# OpIoT_jetson_v_1_5.net
KiCad netlist of a schematic drawn in EAGLE
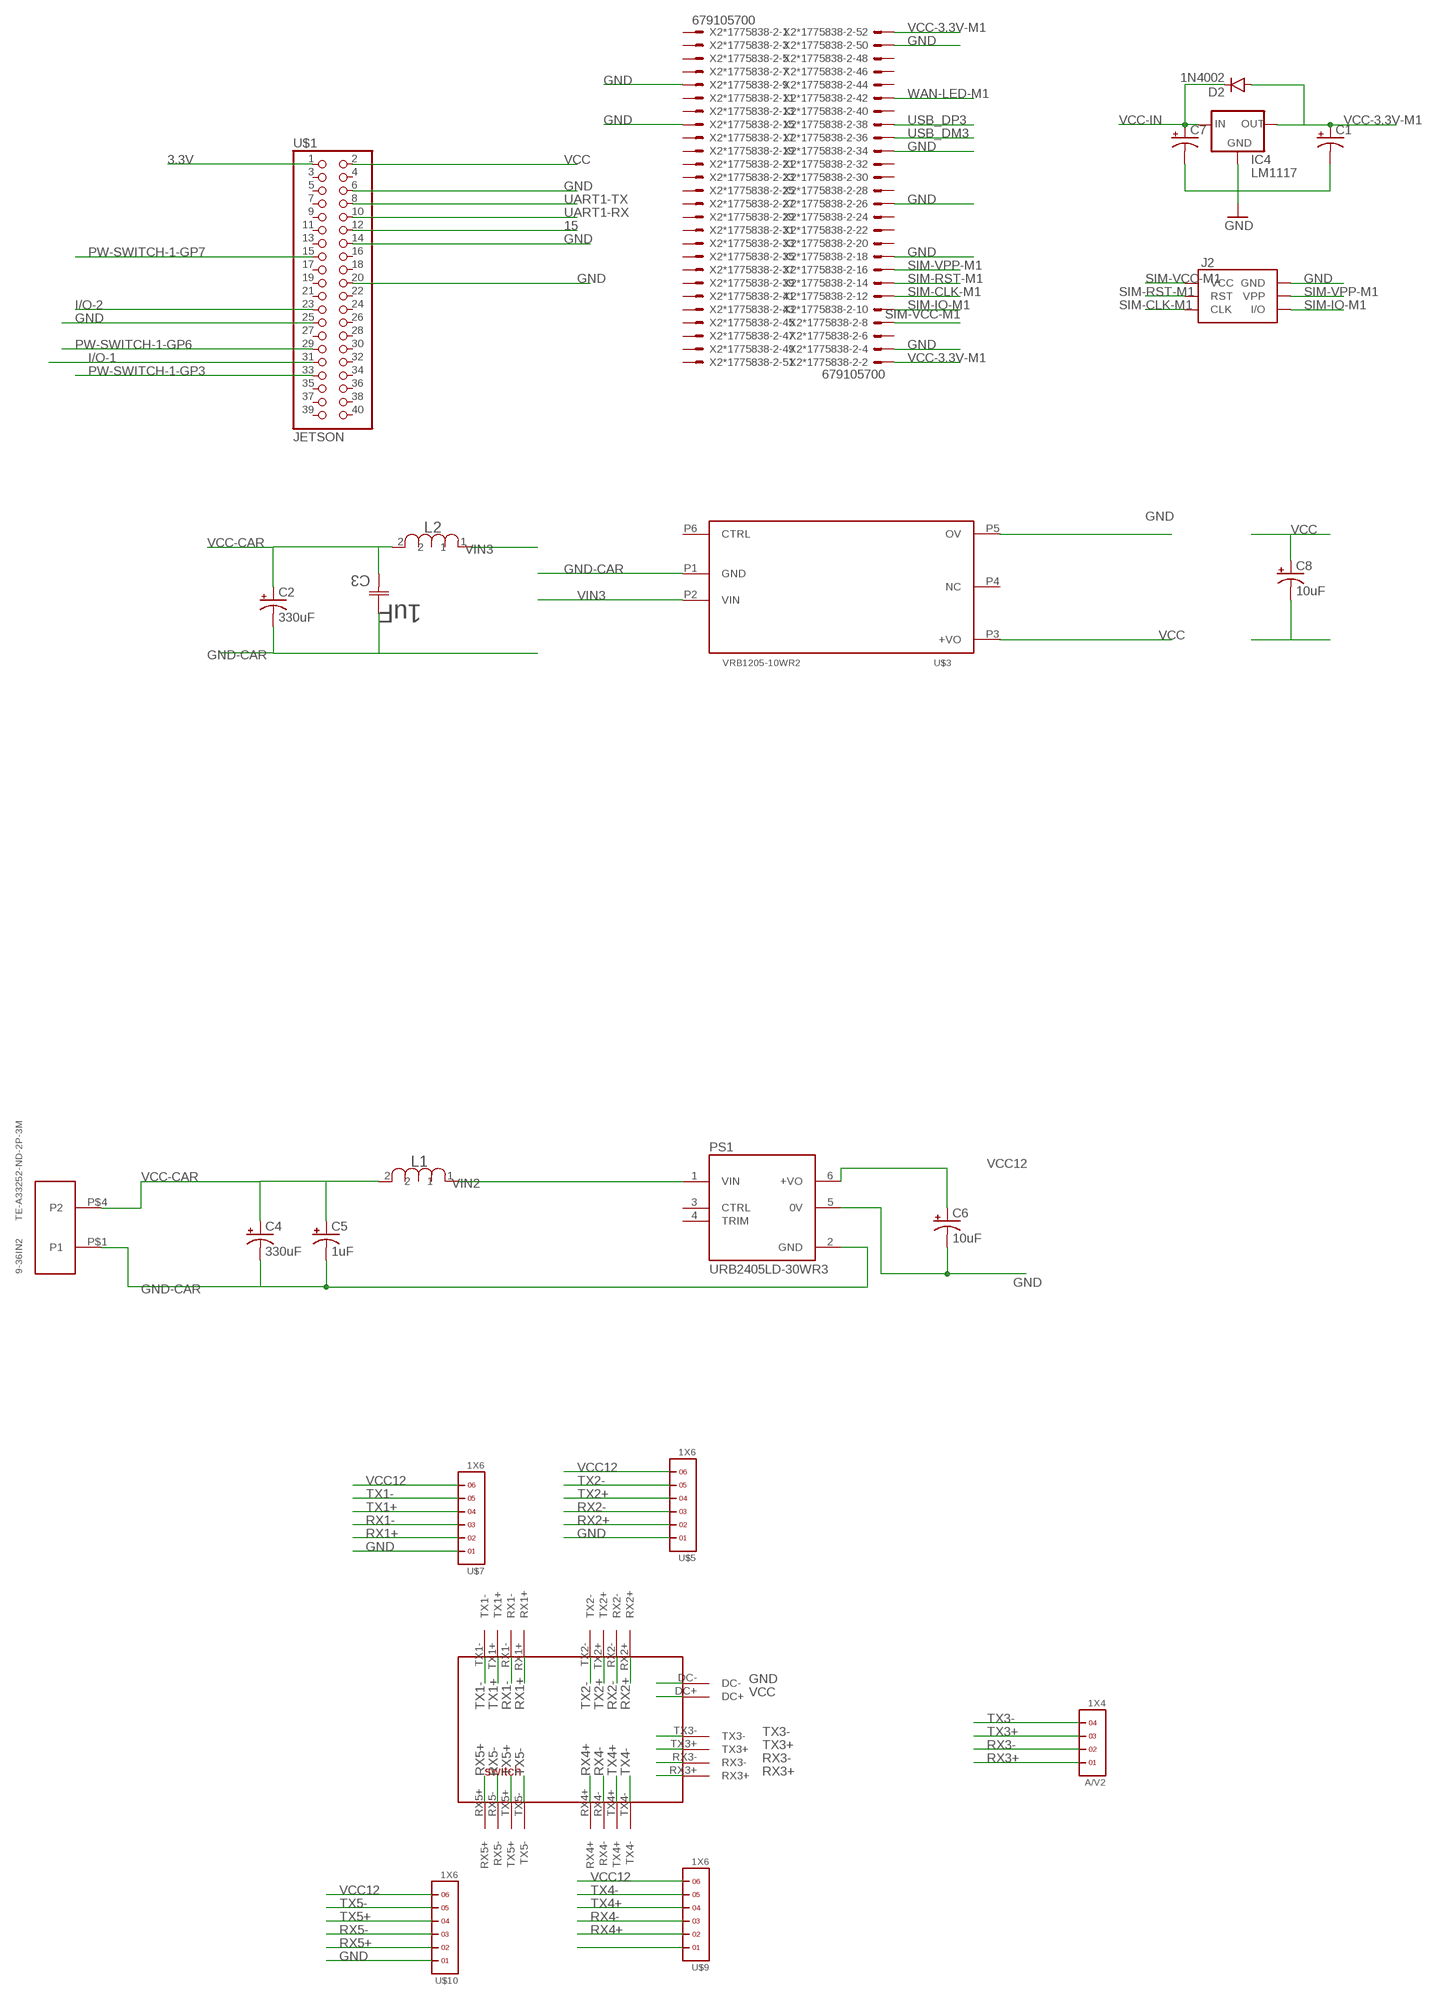
[diagram p0: schematic, sheet 1, part 1 of 3]
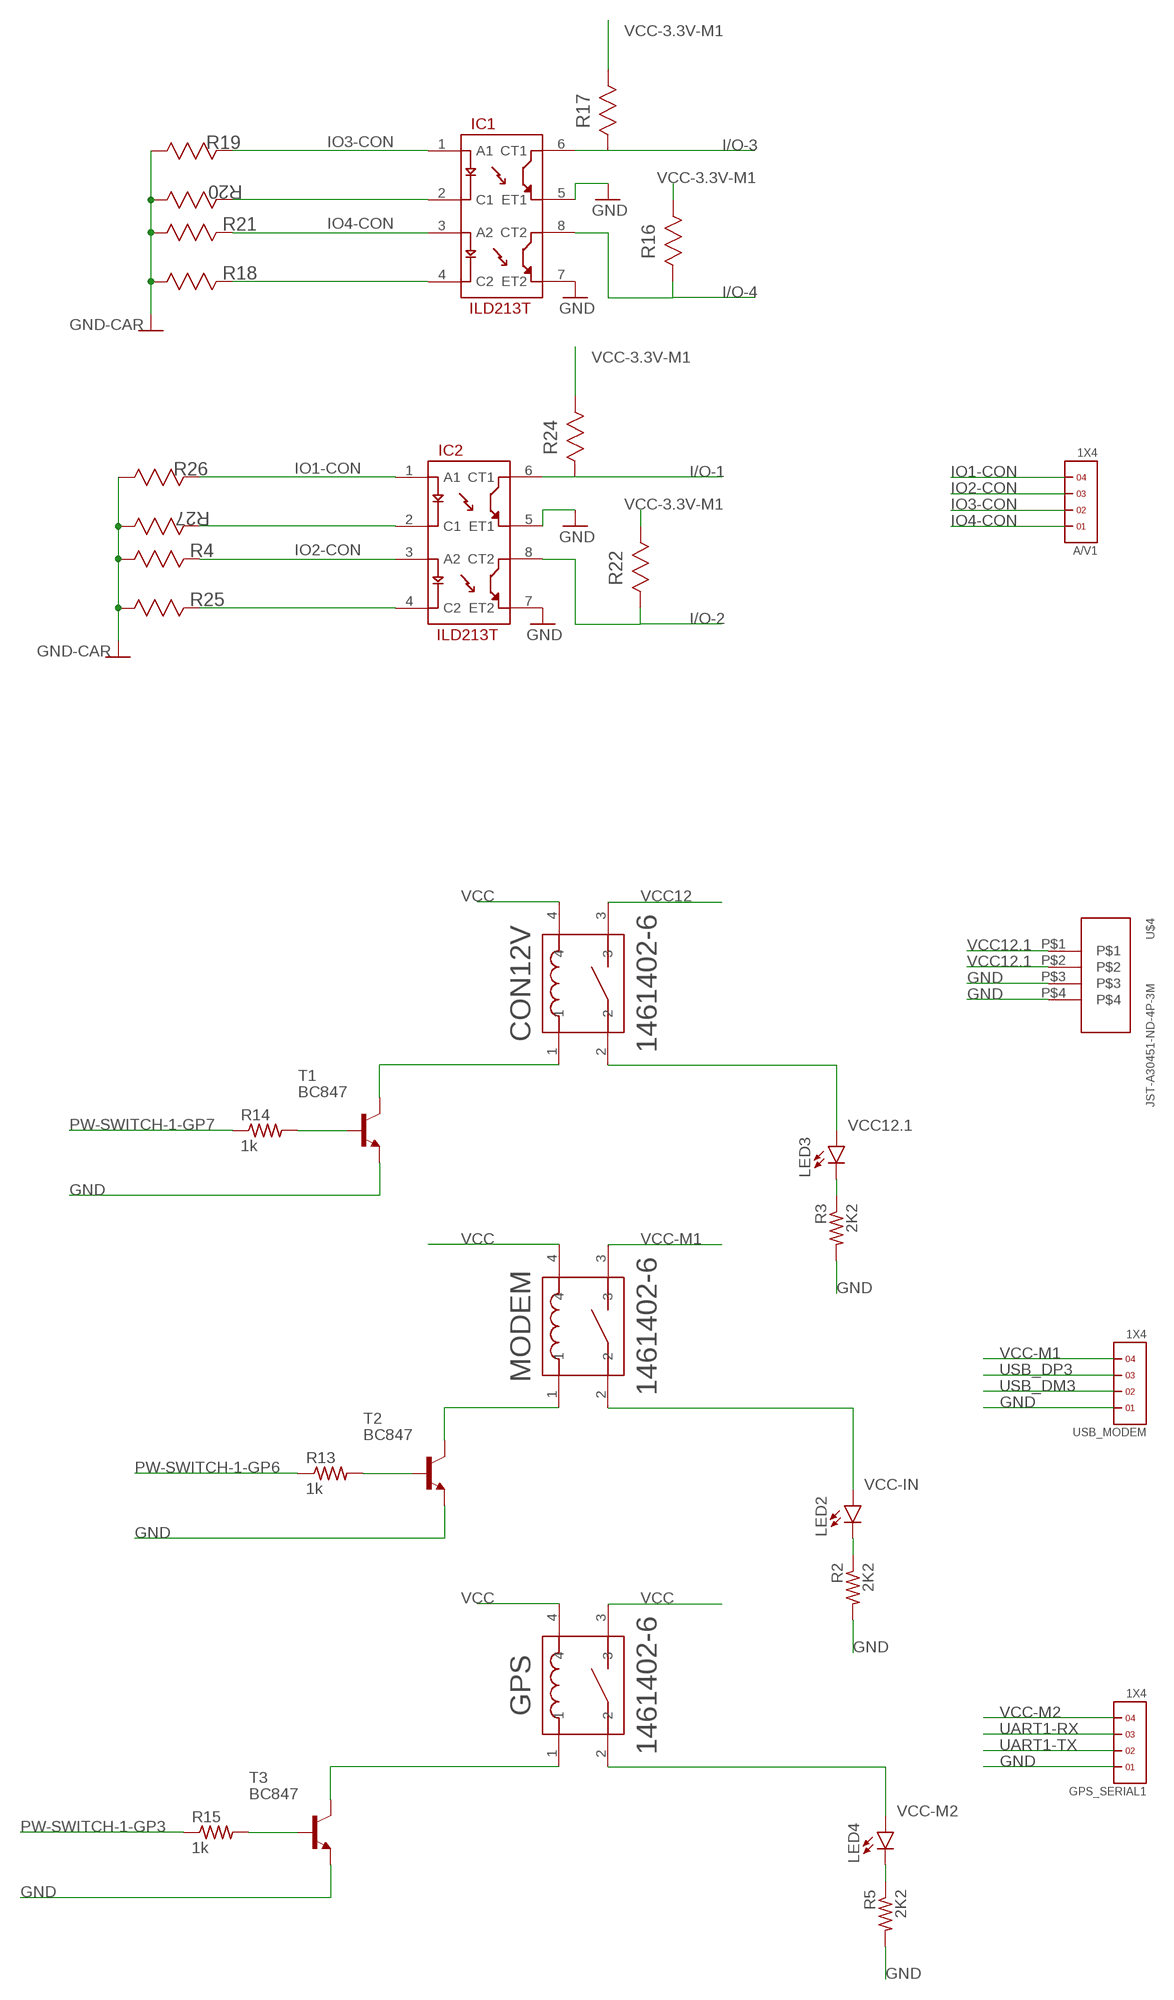
[diagram p1: schematic, sheet 1, part 2 of 3]
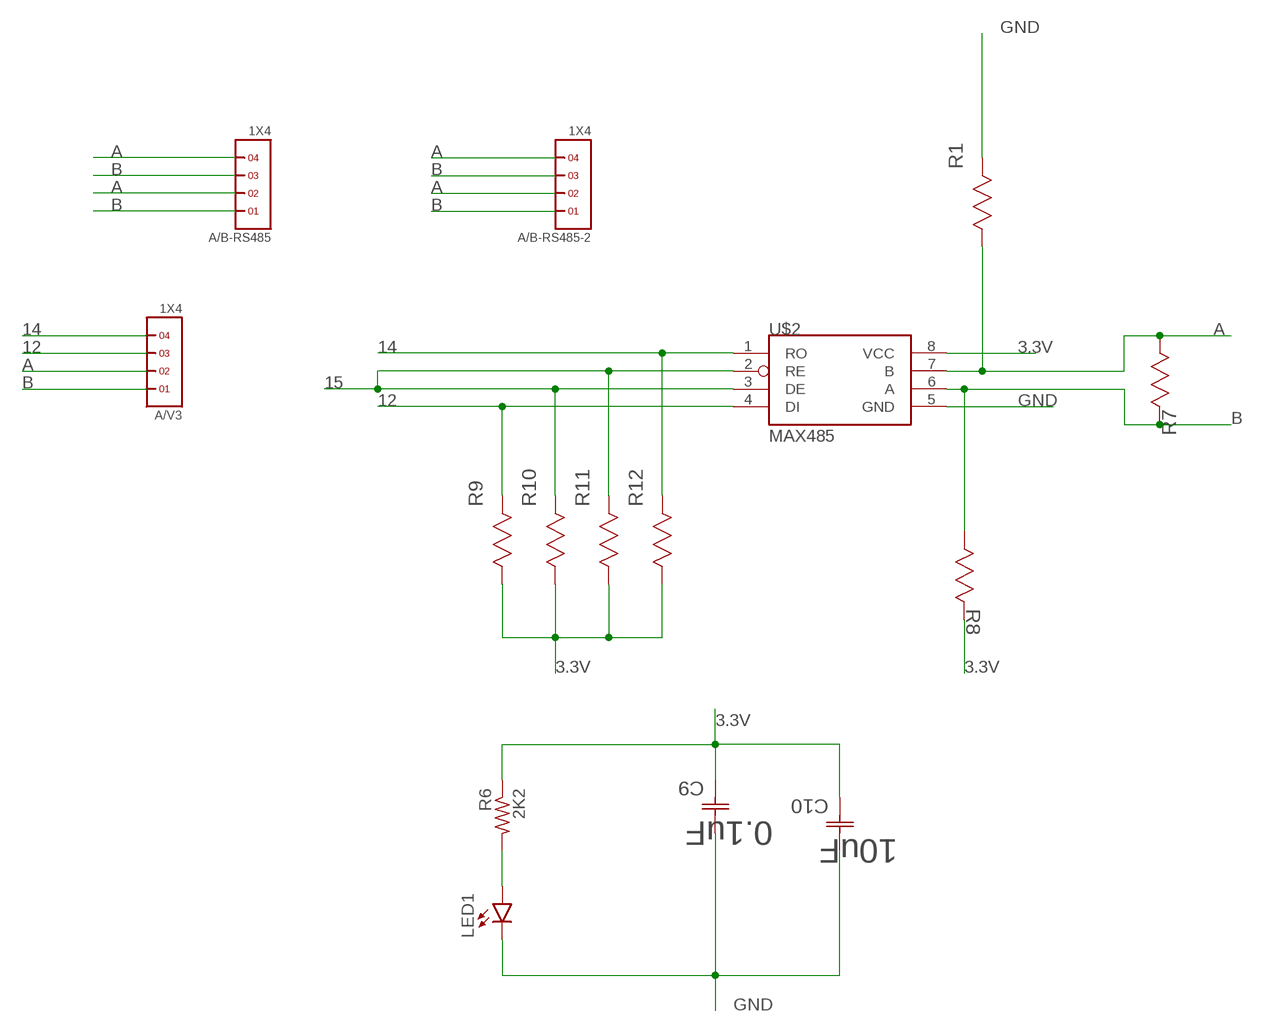
[diagram p2: schematic, sheet 1, part 3 of 3]

(export (version "E")
  (design (tool "Eeschema 10.0.6"))
  (components
    (comp (ref "9-36IN2")
      (value "TE-A33252-ND-2P-3M")
      (footprint "eagle-import:TE-A33252-ND-2P-3M")
      (libsource (lib "eagle-import") (part "TE-A33252-ND-2P-3M"))
    )
    (comp (ref "A/B-RS485")
      (value "1X4")
      (footprint "eagle-import:1X4")
      (libsource (lib "eagle-import") (part "1X4"))
    )
    (comp (ref "A/B-RS485-2")
      (value "1X4")
      (footprint "eagle-import:1X4")
      (libsource (lib "eagle-import") (part "1X4"))
    )
    (comp (ref "A/V1")
      (value "1X4")
      (footprint "eagle-import:1X4")
      (libsource (lib "eagle-import") (part "1X4"))
    )
    (comp (ref "A/V2")
      (value "1X4")
      (footprint "eagle-import:1X4")
      (libsource (lib "eagle-import") (part "1X4"))
    )
    (comp (ref "A/V3")
      (value "1X4")
      (footprint "eagle-import:1X4")
      (libsource (lib "eagle-import") (part "1X4"))
    )
    (comp (ref "C1")
      (value "CAP_POL1206-KIT")
      (footprint "eagle-import:EIA3216-KIT")
      (libsource (lib "eagle-import") (part "CAP_POL1206-KIT"))
    )
    (comp (ref "C2")
      (value "330uF")
      (footprint "eagle-import:UD-10X10_NICHICON")
      (libsource (lib "eagle-import") (part "CPOL-USUD-10X10"))
    )
    (comp (ref "C3")
      (value "1uF")
      (footprint "eagle-import:CAPC3216X110N")
      (fields (field (name "MPN") "C1206C105K5RACTU") (field (name "TOLERANCE") "±10%"))
      (libsource (lib "eagle-import") (part "C1206C105K5RACTU"))
    )
    (comp (ref "C4")
      (value "330uF")
      (footprint "eagle-import:UD-10X10_NICHICON")
      (libsource (lib "eagle-import") (part "CPOL-USUD-10X10"))
    )
    (comp (ref "C5")
      (value "1uF")
      (footprint "eagle-import:EIA3216-KIT")
      (libsource (lib "eagle-import") (part "CAP_POL1206-KIT"))
    )
    (comp (ref "C6")
      (value "10uF")
      (footprint "eagle-import:EIA3216-KIT")
      (libsource (lib "eagle-import") (part "CAP_POL1206-KIT"))
    )
    (comp (ref "C7")
      (value "CAP_POL1206-KIT")
      (footprint "eagle-import:EIA3216-KIT")
      (libsource (lib "eagle-import") (part "CAP_POL1206-KIT"))
    )
    (comp (ref "C8")
      (value "10uF")
      (footprint "eagle-import:EIA3216-KIT")
      (libsource (lib "eagle-import") (part "CAP_POL1206-KIT"))
    )
    (comp (ref "C9")
      (value "0.1uF")
      (footprint "eagle-import:CAPC3216X110N")
      (fields (field (name "MPN") "C1206C105K5RACTU") (field (name "TOLERANCE") "±10%"))
      (libsource (lib "eagle-import") (part "C1206C105K5RACTU"))
    )
    (comp (ref "C10")
      (value "10uF")
      (footprint "eagle-import:CAPC3216X110N")
      (fields (field (name "MPN") "C1206C105K5RACTU") (field (name "TOLERANCE") "±10%"))
      (libsource (lib "eagle-import") (part "C1206C105K5RACTU"))
    )
    (comp (ref "CON12V")
      (value "1461402-6")
      (footprint "eagle-import:RELAY_1461402-6")
      (fields (field (name "MF") "TE Connectivity") (field (name "MP") "OJE-SH-112HM,000"))
      (libsource (lib "eagle-import") (part "1461402-6"))
    )
    (comp (ref "D2")
      (value "1N4002")
      (footprint "eagle-import:SMA-DIODE-KIT")
      (libsource (lib "eagle-import") (part "DIODESMA-KIT"))
    )
    (comp (ref "GPS")
      (value "1461402-6")
      (footprint "eagle-import:RELAY_1461402-6")
      (fields (field (name "MF") "TE Connectivity") (field (name "MP") "OJE-SH-112HM,000"))
      (libsource (lib "eagle-import") (part "1461402-6"))
    )
    (comp (ref "GPS_SERIAL1")
      (value "1X4")
      (footprint "eagle-import:1X4")
      (libsource (lib "eagle-import") (part "1X4"))
    )
    (comp (ref "IC1")
      (value "ILD213T")
      (footprint "eagle-import:SO08")
      (libsource (lib "eagle-import") (part "ILD213T"))
    )
    (comp (ref "IC2")
      (value "ILD213T")
      (footprint "eagle-import:SO08")
      (libsource (lib "eagle-import") (part "ILD213T"))
    )
    (comp (ref "IC4")
      (value "LM1117")
      (footprint "eagle-import:SOT223")
      (fields (field (name "MF") "Texas Instruments") (field (name "MP") "LM1117MP-3.3/NOPB"))
      (libsource (lib "eagle-import") (part "LM1117"))
    )
    (comp (ref "J2")
      (value "SIMHOLDERSIM")
      (footprint "eagle-import:SIMHOLDER")
      (libsource (lib "eagle-import") (part "SIMHOLDERSIM"))
    )
    (comp (ref "L1")
      (value "4.7uH")
      (footprint "eagle-import:INDC3225X22N")
      (fields (field (name "MPN") "PM1210-1R0J-RC") (field (name "TOLERANCE") "±5 %"))
      (libsource (lib "eagle-import") (part "PM1210-1R0J-RC"))
    )
    (comp (ref "L2")
      (value "4.7uH")
      (footprint "eagle-import:INDC3225X22N")
      (fields (field (name "MPN") "PM1210-1R0J-RC") (field (name "TOLERANCE") "±5 %"))
      (libsource (lib "eagle-import") (part "PM1210-1R0J-RC"))
    )
    (comp (ref "LED1")
      (value "LEDCHIPLED_1206")
      (footprint "eagle-import:CHIPLED_1206")
      (libsource (lib "eagle-import") (part "LEDCHIPLED_1206"))
    )
    (comp (ref "LED2")
      (value "LEDCHIPLED_1206")
      (footprint "eagle-import:CHIPLED_1206")
      (libsource (lib "eagle-import") (part "LEDCHIPLED_1206"))
    )
    (comp (ref "LED3")
      (value "LEDCHIPLED_1206")
      (footprint "eagle-import:CHIPLED_1206")
      (libsource (lib "eagle-import") (part "LEDCHIPLED_1206"))
    )
    (comp (ref "LED4")
      (value "LEDCHIPLED_1206")
      (footprint "eagle-import:CHIPLED_1206")
      (libsource (lib "eagle-import") (part "LEDCHIPLED_1206"))
    )
    (comp (ref "MODEM")
      (value "1461402-6")
      (footprint "eagle-import:RELAY_1461402-6")
      (fields (field (name "MF") "TE Connectivity") (field (name "MP") "OJE-SH-112HM,000"))
      (libsource (lib "eagle-import") (part "1461402-6"))
    )
    (comp (ref "PS1")
      (value "URB2405LD-30WR3")
      (footprint "eagle-import:CONV_URB2405LD-30WR3")
      (fields (field (name "MF") "MORNSUN"))
      (libsource (lib "eagle-import") (part "URB2405LD-30WR3"))
    )
    (comp (ref "R1")
      (value "20K")
      (footprint "eagle-import:RESC3216X71N")
      (fields (field (name "MPN") "ERJ-8ENF1501V") (field (name "TOLERANCE") "±1 %"))
      (libsource (lib "eagle-import") (part "ERJ-8ENF1501V"))
    )
    (comp (ref "R2")
      (value "2K2")
      (footprint "eagle-import:M1206")
      (libsource (lib "eagle-import") (part "R-US_M1206"))
    )
    (comp (ref "R3")
      (value "2K2")
      (footprint "eagle-import:M1206")
      (libsource (lib "eagle-import") (part "R-US_M1206"))
    )
    (comp (ref "R4")
      (value "4K7")
      (footprint "eagle-import:RESC3216X71N")
      (fields (field (name "MPN") "ERJ-8ENF1501V") (field (name "TOLERANCE") "±1 %"))
      (libsource (lib "eagle-import") (part "ERJ-8ENF1501V"))
    )
    (comp (ref "R5")
      (value "2K2")
      (footprint "eagle-import:M1206")
      (libsource (lib "eagle-import") (part "R-US_M1206"))
    )
    (comp (ref "R6")
      (value "2K2")
      (footprint "eagle-import:M1206")
      (libsource (lib "eagle-import") (part "R-US_M1206"))
    )
    (comp (ref "R7")
      (value "120")
      (footprint "eagle-import:RESC3216X71N")
      (fields (field (name "MPN") "ERJ-8ENF1501V") (field (name "TOLERANCE") "±1 %"))
      (libsource (lib "eagle-import") (part "ERJ-8ENF1501V"))
    )
    (comp (ref "R8")
      (value "20k")
      (footprint "eagle-import:RESC3216X71N")
      (fields (field (name "MPN") "ERJ-8ENF1501V") (field (name "TOLERANCE") "±1 %"))
      (libsource (lib "eagle-import") (part "ERJ-8ENF1501V"))
    )
    (comp (ref "R9")
      (value "10k")
      (footprint "eagle-import:RESC3216X71N")
      (fields (field (name "MPN") "ERJ-8ENF1501V") (field (name "TOLERANCE") "±1 %"))
      (libsource (lib "eagle-import") (part "ERJ-8ENF1501V"))
    )
    (comp (ref "R10")
      (value "10k")
      (footprint "eagle-import:RESC3216X71N")
      (fields (field (name "MPN") "ERJ-8ENF1501V") (field (name "TOLERANCE") "±1 %"))
      (libsource (lib "eagle-import") (part "ERJ-8ENF1501V"))
    )
    (comp (ref "R11")
      (value "10k")
      (footprint "eagle-import:RESC3216X71N")
      (fields (field (name "MPN") "ERJ-8ENF1501V") (field (name "TOLERANCE") "±1 %"))
      (libsource (lib "eagle-import") (part "ERJ-8ENF1501V"))
    )
    (comp (ref "R12")
      (value "10k")
      (footprint "eagle-import:RESC3216X71N")
      (fields (field (name "MPN") "ERJ-8ENF1501V") (field (name "TOLERANCE") "±1 %"))
      (libsource (lib "eagle-import") (part "ERJ-8ENF1501V"))
    )
    (comp (ref "R13")
      (value "1k")
      (footprint "eagle-import:M1406")
      (libsource (lib "eagle-import") (part "R-US_M1406"))
    )
    (comp (ref "R14")
      (value "1k")
      (footprint "eagle-import:M1406")
      (libsource (lib "eagle-import") (part "R-US_M1406"))
    )
    (comp (ref "R15")
      (value "1k")
      (footprint "eagle-import:M1406")
      (libsource (lib "eagle-import") (part "R-US_M1406"))
    )
    (comp (ref "R16")
      (value "300K")
      (footprint "eagle-import:RESC3216X71N")
      (fields (field (name "MPN") "ERJ-8ENF1501V") (field (name "TOLERANCE") "±1 %"))
      (libsource (lib "eagle-import") (part "ERJ-8ENF1501V"))
    )
    (comp (ref "R17")
      (value "300K")
      (footprint "eagle-import:RESC3216X71N")
      (fields (field (name "MPN") "ERJ-8ENF1501V") (field (name "TOLERANCE") "±1 %"))
      (libsource (lib "eagle-import") (part "ERJ-8ENF1501V"))
    )
    (comp (ref "R18")
      (value "2.2K")
      (footprint "eagle-import:RESC3216X71N")
      (fields (field (name "MPN") "ERJ-8ENF1501V") (field (name "TOLERANCE") "±1 %"))
      (libsource (lib "eagle-import") (part "ERJ-8ENF1501V"))
    )
    (comp (ref "R19")
      (value "4K7")
      (footprint "eagle-import:RESC3216X71N")
      (fields (field (name "MPN") "ERJ-8ENF1501V") (field (name "TOLERANCE") "±1 %"))
      (libsource (lib "eagle-import") (part "ERJ-8ENF1501V"))
    )
    (comp (ref "R20")
      (value "2.2K")
      (footprint "eagle-import:RESC3216X71N")
      (fields (field (name "MPN") "ERJ-8ENF1501V") (field (name "TOLERANCE") "±1 %"))
      (libsource (lib "eagle-import") (part "ERJ-8ENF1501V"))
    )
    (comp (ref "R21")
      (value "4K7")
      (footprint "eagle-import:RESC3216X71N")
      (fields (field (name "MPN") "ERJ-8ENF1501V") (field (name "TOLERANCE") "±1 %"))
      (libsource (lib "eagle-import") (part "ERJ-8ENF1501V"))
    )
    (comp (ref "R22")
      (value "300K")
      (footprint "eagle-import:RESC3216X71N")
      (fields (field (name "MPN") "ERJ-8ENF1501V") (field (name "TOLERANCE") "±1 %"))
      (libsource (lib "eagle-import") (part "ERJ-8ENF1501V"))
    )
    (comp (ref "R24")
      (value "300K")
      (footprint "eagle-import:RESC3216X71N")
      (fields (field (name "MPN") "ERJ-8ENF1501V") (field (name "TOLERANCE") "±1 %"))
      (libsource (lib "eagle-import") (part "ERJ-8ENF1501V"))
    )
    (comp (ref "R25")
      (value "2.2K")
      (footprint "eagle-import:RESC3216X71N")
      (fields (field (name "MPN") "ERJ-8ENF1501V") (field (name "TOLERANCE") "±1 %"))
      (libsource (lib "eagle-import") (part "ERJ-8ENF1501V"))
    )
    (comp (ref "R26")
      (value "ERJ-8ENF1501V")
      (footprint "eagle-import:RESC3216X71N")
      (fields (field (name "TOLERANCE") "±1 %"))
      (libsource (lib "eagle-import") (part "ERJ-8ENF1501V"))
    )
    (comp (ref "R27")
      (value "2.2K")
      (footprint "eagle-import:RESC3216X71N")
      (fields (field (name "MPN") "ERJ-8ENF1501V") (field (name "TOLERANCE") "±1 %"))
      (libsource (lib "eagle-import") (part "ERJ-8ENF1501V"))
    )
    (comp (ref "T1")
      (value "BC847")
      (footprint "eagle-import:SOT23")
      (libsource (lib "eagle-import") (part "BC847"))
    )
    (comp (ref "T2")
      (value "BC847")
      (footprint "eagle-import:SOT23")
      (libsource (lib "eagle-import") (part "BC847"))
    )
    (comp (ref "T3")
      (value "BC847")
      (footprint "eagle-import:SOT23")
      (libsource (lib "eagle-import") (part "BC847"))
    )
    (comp (ref "U$1")
      (value "JETSON")
      (footprint "eagle-import:2X20")
      (libsource (lib "eagle-import") (part "JETSON"))
    )
    (comp (ref "U$2")
      (value "MAX485")
      (footprint "eagle-import:SO08")
      (fields (field (name "MF") "Maxim Integrated"))
      (libsource (lib "eagle-import") (part "MAX485"))
    )
    (comp (ref "U$3")
      (value "VRB1205-10WR2")
      (footprint "eagle-import:MORNSUN-5V")
      (libsource (lib "eagle-import") (part "VRB1205-10WR2"))
    )
    (comp (ref "U$4")
      (value "JST-A30451-ND-4P-3M")
      (footprint "eagle-import:TE-A30451-4P-TH-3M")
      (libsource (lib "eagle-import") (part "JST-A30451-ND-4P-3M"))
    )
    (comp (ref "U$5")
      (value "1X6")
      (footprint "eagle-import:1X6")
      (libsource (lib "eagle-import") (part "1X6"))
    )
    (comp (ref "U$6")
      (value "SWITCH")
      (footprint "eagle-import:JP4")
      (libsource (lib "eagle-import") (part "SWITCH"))
    )
    (comp (ref "U$7")
      (value "1X6")
      (footprint "eagle-import:1X6")
      (libsource (lib "eagle-import") (part "1X6"))
    )
    (comp (ref "U$9")
      (value "1X6")
      (footprint "eagle-import:1X6")
      (libsource (lib "eagle-import") (part "1X6"))
    )
    (comp (ref "U$10")
      (value "1X6")
      (footprint "eagle-import:1X6")
      (libsource (lib "eagle-import") (part "1X6"))
    )
    (comp (ref "USB_MODEM")
      (value "1X4")
      (footprint "eagle-import:1X4")
      (libsource (lib "eagle-import") (part "1X4"))
    )
    (comp (ref "X2*1775838-2")
      (value "679105700")
      (footprint "eagle-import:679105700")
      (fields (field (name "MF") "MOLEX") (field (name "MPN") "67910-5700"))
      (libsource (lib "eagle-import") (part "679105700"))
    )
  )
  (nets
    (net (code "1") (name "/3.3V") (class "Default")
      (node (ref "C10") (pin "2") (pinfunction "C2_2") (pintype "passive"))
      (node (ref "C9") (pin "2") (pinfunction "C2_2") (pintype "passive"))
      (node (ref "R10") (pin "2") (pinfunction "R2_2") (pintype "passive"))
      (node (ref "R11") (pin "2") (pinfunction "R2_2") (pintype "passive"))
      (node (ref "R12") (pin "2") (pinfunction "R2_2") (pintype "passive"))
      (node (ref "R6") (pin "1") (pinfunction "1_1") (pintype "passive"))
      (node (ref "R8") (pin "1") (pinfunction "R1_1") (pintype "passive"))
      (node (ref "R9") (pin "2") (pinfunction "R2_2") (pintype "passive"))
      (node (ref "U$1") (pin "1") (pinfunction "1_1") (pintype "passive"))
      (node (ref "U$2") (pin "8") (pinfunction "VCC_8") (pintype "bidirectional"))
    )
    (net (code "2") (name "/12") (class "Default")
      (node (ref "A/V3") (pin "3") (pinfunction "3_3") (pintype "bidirectional"))
      (node (ref "R9") (pin "1") (pinfunction "R1_1") (pintype "passive"))
      (node (ref "U$2") (pin "4") (pinfunction "DI_4") (pintype "bidirectional"))
    )
    (net (code "3") (name "/14") (class "Default")
      (node (ref "A/V3") (pin "4") (pinfunction "4_4") (pintype "bidirectional"))
      (node (ref "R12") (pin "1") (pinfunction "R1_1") (pintype "passive"))
      (node (ref "U$2") (pin "1") (pinfunction "RO_1") (pintype "bidirectional"))
    )
    (net (code "4") (name "/15") (class "Default")
      (node (ref "R10") (pin "1") (pinfunction "R1_1") (pintype "passive"))
      (node (ref "R11") (pin "1") (pinfunction "R1_1") (pintype "passive"))
      (node (ref "U$1") (pin "12") (pinfunction "12_12") (pintype "passive"))
      (node (ref "U$2") (pin "2") (pinfunction "RE_2") (pintype "bidirectional"))
      (node (ref "U$2") (pin "3") (pinfunction "DE_3") (pintype "bidirectional"))
    )
    (net (code "5") (name "/A") (class "Default")
      (node (ref "A/B-RS485") (pin "2") (pinfunction "2_2") (pintype "bidirectional"))
      (node (ref "A/B-RS485") (pin "4") (pinfunction "4_4") (pintype "bidirectional"))
      (node (ref "A/B-RS485-2") (pin "2") (pinfunction "2_2") (pintype "bidirectional"))
      (node (ref "A/B-RS485-2") (pin "4") (pinfunction "4_4") (pintype "bidirectional"))
      (node (ref "A/V3") (pin "2") (pinfunction "2_2") (pintype "bidirectional"))
      (node (ref "R1") (pin "2") (pinfunction "R2_2") (pintype "passive"))
      (node (ref "R7") (pin "1") (pinfunction "R1_1") (pintype "passive"))
      (node (ref "U$2") (pin "7") (pinfunction "B_7") (pintype "bidirectional"))
    )
    (net (code "6") (name "/B") (class "Default")
      (node (ref "A/B-RS485") (pin "1") (pinfunction "1_1") (pintype "bidirectional"))
      (node (ref "A/B-RS485") (pin "3") (pinfunction "3_3") (pintype "bidirectional"))
      (node (ref "A/B-RS485-2") (pin "1") (pinfunction "1_1") (pintype "bidirectional"))
      (node (ref "A/B-RS485-2") (pin "3") (pinfunction "3_3") (pintype "bidirectional"))
      (node (ref "A/V3") (pin "1") (pinfunction "1_1") (pintype "bidirectional"))
      (node (ref "R7") (pin "2") (pinfunction "R2_2") (pintype "passive"))
      (node (ref "R8") (pin "2") (pinfunction "R2_2") (pintype "passive"))
      (node (ref "U$2") (pin "6") (pinfunction "A_6") (pintype "bidirectional"))
    )
    (net (code "7") (name "/IO1-CON") (class "Default")
      (node (ref "A/V1") (pin "4") (pinfunction "4_4") (pintype "bidirectional"))
      (node (ref "IC2") (pin "1") (pinfunction "A1_1") (pintype "bidirectional"))
      (node (ref "R26") (pin "1") (pinfunction "R1_1") (pintype "passive"))
    )
    (net (code "8") (name "/IO2-CON") (class "Default")
      (node (ref "A/V1") (pin "3") (pinfunction "3_3") (pintype "bidirectional"))
      (node (ref "IC2") (pin "3") (pinfunction "A2_3") (pintype "bidirectional"))
      (node (ref "R4") (pin "1") (pinfunction "R1_1") (pintype "passive"))
    )
    (net (code "9") (name "/IO3-CON") (class "Default")
      (node (ref "A/V1") (pin "2") (pinfunction "2_2") (pintype "bidirectional"))
      (node (ref "IC1") (pin "1") (pinfunction "A1_1") (pintype "bidirectional"))
      (node (ref "R19") (pin "1") (pinfunction "R1_1") (pintype "passive"))
    )
    (net (code "10") (name "/IO4-CON") (class "Default")
      (node (ref "A/V1") (pin "1") (pinfunction "1_1") (pintype "bidirectional"))
      (node (ref "IC1") (pin "3") (pinfunction "A2_3") (pintype "bidirectional"))
      (node (ref "R21") (pin "1") (pinfunction "R1_1") (pintype "passive"))
    )
    (net (code "11") (name "/I{slash}O-1") (class "Default")
      (node (ref "IC2") (pin "6") (pinfunction "CT1_6") (pintype "bidirectional"))
      (node (ref "R24") (pin "2") (pinfunction "R2_2") (pintype "passive"))
      (node (ref "U$1") (pin "31") (pinfunction "31_31") (pintype "passive"))
    )
    (net (code "12") (name "/I{slash}O-2") (class "Default")
      (node (ref "IC2") (pin "8") (pinfunction "CT2_8") (pintype "bidirectional"))
      (node (ref "R22") (pin "2") (pinfunction "R2_2") (pintype "passive"))
      (node (ref "U$1") (pin "23") (pinfunction "23_23") (pintype "passive"))
    )
    (net (code "13") (name "/I{slash}O-3") (class "Default")
      (node (ref "IC1") (pin "6") (pinfunction "CT1_6") (pintype "bidirectional"))
      (node (ref "R17") (pin "2") (pinfunction "R2_2") (pintype "passive"))
    )
    (net (code "14") (name "/I{slash}O-4") (class "Default")
      (node (ref "IC1") (pin "8") (pinfunction "CT2_8") (pintype "bidirectional"))
      (node (ref "R16") (pin "2") (pinfunction "R2_2") (pintype "passive"))
    )
    (net (code "15") (name "/PW-SWITCH-1-GP3") (class "Default")
      (node (ref "R15") (pin "1") (pinfunction "1_1") (pintype "passive"))
      (node (ref "U$1") (pin "33") (pinfunction "33_33") (pintype "passive"))
    )
    (net (code "16") (name "/PW-SWITCH-1-GP6") (class "Default")
      (node (ref "R13") (pin "1") (pinfunction "1_1") (pintype "passive"))
      (node (ref "U$1") (pin "29") (pinfunction "29_29") (pintype "passive"))
    )
    (net (code "17") (name "/PW-SWITCH-1-GP7") (class "Default")
      (node (ref "R14") (pin "1") (pinfunction "1_1") (pintype "passive"))
      (node (ref "U$1") (pin "15") (pinfunction "15_15") (pintype "passive"))
    )
    (net (code "18") (name "/RX1+") (class "Default")
      (node (ref "U$6") (pin "RX1+") (pinfunction "RX1+_RX1+") (pintype "bidirectional"))
      (node (ref "U$7") (pin "2") (pinfunction "2_2") (pintype "bidirectional"))
    )
    (net (code "19") (name "/RX1-") (class "Default")
      (node (ref "U$6") (pin "RX1-") (pinfunction "RX1-_RX1-") (pintype "bidirectional"))
      (node (ref "U$7") (pin "3") (pinfunction "3_3") (pintype "bidirectional"))
    )
    (net (code "20") (name "/RX2+") (class "Default")
      (node (ref "U$5") (pin "2") (pinfunction "2_2") (pintype "bidirectional"))
      (node (ref "U$6") (pin "RX2+") (pinfunction "RX2+_RX2+") (pintype "bidirectional"))
    )
    (net (code "21") (name "/RX2-") (class "Default")
      (node (ref "U$5") (pin "3") (pinfunction "3_3") (pintype "bidirectional"))
      (node (ref "U$6") (pin "RX2-") (pinfunction "RX2-_RX2-") (pintype "bidirectional"))
    )
    (net (code "22") (name "/RX3+") (class "Default")
      (node (ref "A/V2") (pin "1") (pinfunction "1_1") (pintype "bidirectional"))
      (node (ref "U$6") (pin "RX3+") (pinfunction "RX3+_RX3+") (pintype "bidirectional"))
    )
    (net (code "23") (name "/RX3-") (class "Default")
      (node (ref "A/V2") (pin "2") (pinfunction "2_2") (pintype "bidirectional"))
      (node (ref "U$6") (pin "RX3-") (pinfunction "RX3-_RX3-") (pintype "bidirectional"))
    )
    (net (code "24") (name "/RX4+") (class "Default")
      (node (ref "U$6") (pin "RX4+") (pinfunction "RX4+_RX4+") (pintype "bidirectional"))
      (node (ref "U$9") (pin "2") (pinfunction "2_2") (pintype "bidirectional"))
    )
    (net (code "25") (name "/RX4-") (class "Default")
      (node (ref "U$6") (pin "RX4-") (pinfunction "RX4-_RX4-") (pintype "bidirectional"))
      (node (ref "U$9") (pin "3") (pinfunction "3_3") (pintype "bidirectional"))
    )
    (net (code "26") (name "/RX5+") (class "Default")
      (node (ref "U$10") (pin "2") (pinfunction "2_2") (pintype "bidirectional"))
      (node (ref "U$6") (pin "RX5+") (pinfunction "RX5+_RX5+") (pintype "bidirectional"))
    )
    (net (code "27") (name "/RX5-") (class "Default")
      (node (ref "U$10") (pin "3") (pinfunction "3_3") (pintype "bidirectional"))
      (node (ref "U$6") (pin "RX5-") (pinfunction "RX5-_RX5-") (pintype "bidirectional"))
    )
    (net (code "28") (name "/SIM-CLK-M1") (class "Default")
      (node (ref "J2") (pin "C3") (pinfunction "CLK_C3") (pintype "input"))
      (node (ref "X2*1775838-2") (pin "12") (pinfunction "S_12") (pintype "passive"))
    )
    (net (code "29") (name "/SIM-IO-M1") (class "Default")
      (node (ref "J2") (pin "C7") (pinfunction "I/O_C7") (pintype "bidirectional"))
      (node (ref "X2*1775838-2") (pin "10") (pinfunction "S_10") (pintype "passive"))
    )
    (net (code "30") (name "/SIM-RST-M1") (class "Default")
      (node (ref "J2") (pin "C2") (pinfunction "RST_C2") (pintype "input"))
      (node (ref "X2*1775838-2") (pin "14") (pinfunction "S_14") (pintype "passive"))
    )
    (net (code "31") (name "/SIM-VCC-M1") (class "Default")
      (node (ref "J2") (pin "C1") (pinfunction "VCC_C1") (pintype "power_in"))
      (node (ref "X2*1775838-2") (pin "8") (pinfunction "S_8") (pintype "passive"))
    )
    (net (code "32") (name "/SIM-VPP-M1") (class "Default")
      (node (ref "J2") (pin "C6") (pinfunction "VPP_C6") (pintype "input"))
      (node (ref "X2*1775838-2") (pin "16") (pinfunction "S_16") (pintype "passive"))
    )
    (net (code "33") (name "/TX1+") (class "Default")
      (node (ref "U$6") (pin "TX1+") (pinfunction "TX1+_TX1+") (pintype "bidirectional"))
      (node (ref "U$7") (pin "4") (pinfunction "4_4") (pintype "bidirectional"))
    )
    (net (code "34") (name "/TX1-") (class "Default")
      (node (ref "U$6") (pin "TX1-") (pinfunction "TX1-_TX1-") (pintype "bidirectional"))
      (node (ref "U$7") (pin "5") (pinfunction "5_5") (pintype "bidirectional"))
    )
    (net (code "35") (name "/TX2+") (class "Default")
      (node (ref "U$5") (pin "4") (pinfunction "4_4") (pintype "bidirectional"))
      (node (ref "U$6") (pin "TX2+") (pinfunction "TX2+_TX2+") (pintype "bidirectional"))
    )
    (net (code "36") (name "/TX2-") (class "Default")
      (node (ref "U$5") (pin "5") (pinfunction "5_5") (pintype "bidirectional"))
      (node (ref "U$6") (pin "TX2-") (pinfunction "TX2-_TX2-") (pintype "bidirectional"))
    )
    (net (code "37") (name "/TX3+") (class "Default")
      (node (ref "A/V2") (pin "3") (pinfunction "3_3") (pintype "bidirectional"))
      (node (ref "U$6") (pin "TX3+") (pinfunction "TX3+_TX3+") (pintype "bidirectional"))
    )
    (net (code "38") (name "/TX3-") (class "Default")
      (node (ref "A/V2") (pin "4") (pinfunction "4_4") (pintype "bidirectional"))
      (node (ref "U$6") (pin "TX3-") (pinfunction "TX3-_TX3-") (pintype "bidirectional"))
    )
    (net (code "39") (name "/TX4+") (class "Default")
      (node (ref "U$6") (pin "TX4+") (pinfunction "TX4+_TX4+") (pintype "bidirectional"))
      (node (ref "U$9") (pin "4") (pinfunction "4_4") (pintype "bidirectional"))
    )
    (net (code "40") (name "/TX4-") (class "Default")
      (node (ref "U$6") (pin "TX4-") (pinfunction "TX4-_TX4-") (pintype "bidirectional"))
      (node (ref "U$9") (pin "5") (pinfunction "5_5") (pintype "bidirectional"))
    )
    (net (code "41") (name "/TX5+") (class "Default")
      (node (ref "U$10") (pin "4") (pinfunction "4_4") (pintype "bidirectional"))
      (node (ref "U$6") (pin "TX5+") (pinfunction "TX5+_TX5+") (pintype "bidirectional"))
    )
    (net (code "42") (name "/TX5-") (class "Default")
      (node (ref "U$10") (pin "5") (pinfunction "5_5") (pintype "bidirectional"))
      (node (ref "U$6") (pin "TX5-") (pinfunction "TX5-_TX5-") (pintype "bidirectional"))
    )
    (net (code "43") (name "/UART1-RX") (class "Default")
      (node (ref "GPS_SERIAL1") (pin "3") (pinfunction "3_3") (pintype "bidirectional"))
      (node (ref "U$1") (pin "10") (pinfunction "10_10") (pintype "passive"))
    )
    (net (code "44") (name "/UART1-TX") (class "Default")
      (node (ref "GPS_SERIAL1") (pin "2") (pinfunction "2_2") (pintype "bidirectional"))
      (node (ref "U$1") (pin "8") (pinfunction "8_8") (pintype "passive"))
    )
    (net (code "45") (name "/USB_DM3") (class "Default")
      (node (ref "USB_MODEM") (pin "2") (pinfunction "2_2") (pintype "bidirectional"))
      (node (ref "X2*1775838-2") (pin "36") (pinfunction "S_36") (pintype "passive"))
    )
    (net (code "46") (name "/USB_DP3") (class "Default")
      (node (ref "USB_MODEM") (pin "3") (pinfunction "3_3") (pintype "bidirectional"))
      (node (ref "X2*1775838-2") (pin "38") (pinfunction "S_38") (pintype "passive"))
    )
    (net (code "47") (name "/VCC") (class "Default")
      (node (ref "C8") (pin "A") (pinfunction "+_A") (pintype "passive"))
      (node (ref "CON12V") (pin "4") (pinfunction "4_4") (pintype "passive"))
      (node (ref "GPS") (pin "3") (pinfunction "3_3") (pintype "passive"))
      (node (ref "GPS") (pin "4") (pinfunction "4_4") (pintype "passive"))
      (node (ref "MODEM") (pin "4") (pinfunction "4_4") (pintype "passive"))
      (node (ref "U$1") (pin "2") (pinfunction "2_2") (pintype "passive"))
      (node (ref "U$3") (pin "P3") (pinfunction "+VO_P3") (pintype "output"))
      (node (ref "U$6") (pin "DC+") (pinfunction "DC+_DC+") (pintype "bidirectional"))
    )
    (net (code "48") (name "/VCC-3.3V-M1") (class "Default")
      (node (ref "C1") (pin "A") (pinfunction "+_A") (pintype "passive"))
      (node (ref "D2") (pin "A") (pinfunction "A_A") (pintype "passive"))
      (node (ref "IC4") (pin "2") (pinfunction "OUT_2") (pintype "passive"))
      (node (ref "R16") (pin "1") (pinfunction "R1_1") (pintype "passive"))
      (node (ref "R17") (pin "1") (pinfunction "R1_1") (pintype "passive"))
      (node (ref "R22") (pin "1") (pinfunction "R1_1") (pintype "passive"))
      (node (ref "R24") (pin "1") (pinfunction "R1_1") (pintype "passive"))
      (node (ref "X2*1775838-2") (pin "2") (pinfunction "S_2") (pintype "passive"))
      (node (ref "X2*1775838-2") (pin "52") (pinfunction "S_52") (pintype "passive"))
    )
    (net (code "49") (name "/VCC-CAR") (class "Default")
      (node (ref "9-36IN2") (pin "P$4") (pinfunction "P2_P$4") (pintype "bidirectional"))
      (node (ref "C2") (pin "+") (pinfunction "+_+") (pintype "passive"))
      (node (ref "C3") (pin "2") (pinfunction "C2_2") (pintype "passive"))
      (node (ref "C4") (pin "+") (pinfunction "+_+") (pintype "passive"))
      (node (ref "C5") (pin "A") (pinfunction "+_A") (pintype "passive"))
      (node (ref "L1") (pin "2") (pinfunction "2_2") (pintype "passive"))
      (node (ref "L2") (pin "2") (pinfunction "2_2") (pintype "passive"))
    )
    (net (code "50") (name "/VCC-IN") (class "Default")
      (node (ref "C7") (pin "A") (pinfunction "+_A") (pintype "passive"))
      (node (ref "D2") (pin "C") (pinfunction "C_C") (pintype "passive"))
      (node (ref "IC4") (pin "3") (pinfunction "IN_3") (pintype "input"))
      (node (ref "LED2") (pin "A") (pinfunction "A_A") (pintype "passive"))
      (node (ref "MODEM") (pin "2") (pinfunction "2_2") (pintype "passive"))
    )
    (net (code "51") (name "/VCC-M1") (class "Default")
      (node (ref "MODEM") (pin "3") (pinfunction "3_3") (pintype "passive"))
      (node (ref "USB_MODEM") (pin "4") (pinfunction "4_4") (pintype "bidirectional"))
    )
    (net (code "52") (name "/VCC-M2") (class "Default")
      (node (ref "GPS") (pin "2") (pinfunction "2_2") (pintype "passive"))
      (node (ref "GPS_SERIAL1") (pin "4") (pinfunction "4_4") (pintype "bidirectional"))
      (node (ref "LED4") (pin "A") (pinfunction "A_A") (pintype "passive"))
    )
    (net (code "53") (name "/VCC12") (class "Default")
      (node (ref "C6") (pin "A") (pinfunction "+_A") (pintype "passive"))
      (node (ref "CON12V") (pin "3") (pinfunction "3_3") (pintype "passive"))
      (node (ref "PS1") (pin "6") (pinfunction "+VO_6") (pintype "output"))
      (node (ref "U$10") (pin "6") (pinfunction "6_6") (pintype "bidirectional"))
      (node (ref "U$5") (pin "6") (pinfunction "6_6") (pintype "bidirectional"))
      (node (ref "U$7") (pin "6") (pinfunction "6_6") (pintype "bidirectional"))
      (node (ref "U$9") (pin "6") (pinfunction "6_6") (pintype "bidirectional"))
    )
    (net (code "54") (name "/VCC12.1") (class "Default")
      (node (ref "CON12V") (pin "2") (pinfunction "2_2") (pintype "passive"))
      (node (ref "LED3") (pin "A") (pinfunction "A_A") (pintype "passive"))
      (node (ref "U$4") (pin "P$1") (pinfunction "P$1_P$1") (pintype "bidirectional"))
      (node (ref "U$4") (pin "P$2") (pinfunction "P$2_P$2") (pintype "bidirectional"))
    )
    (net (code "55") (name "/VIN2") (class "Default")
      (node (ref "L1") (pin "1") (pinfunction "1_1") (pintype "passive"))
      (node (ref "PS1") (pin "1") (pinfunction "VIN_1") (pintype "input"))
    )
    (net (code "56") (name "/VIN3") (class "Default")
      (node (ref "L2") (pin "1") (pinfunction "1_1") (pintype "passive"))
      (node (ref "U$3") (pin "P2") (pinfunction "VIN_P2") (pintype "bidirectional"))
    )
    (net (code "57") (name "/WAN-LED-M1") (class "Default")
      (node (ref "X2*1775838-2") (pin "42") (pinfunction "S_42") (pintype "passive"))
    )
    (net (code "58") (name "GND") (class "Default")
      (node (ref "C1") (pin "C") (pinfunction "-_C") (pintype "passive"))
      (node (ref "C10") (pin "1") (pinfunction "C1_1") (pintype "passive"))
      (node (ref "C6") (pin "C") (pinfunction "-_C") (pintype "passive"))
      (node (ref "C7") (pin "C") (pinfunction "-_C") (pintype "passive"))
      (node (ref "C8") (pin "C") (pinfunction "-_C") (pintype "passive"))
      (node (ref "C9") (pin "1") (pinfunction "C1_1") (pintype "passive"))
      (node (ref "GPS_SERIAL1") (pin "1") (pinfunction "1_1") (pintype "bidirectional"))
      (node (ref "IC1") (pin "5") (pinfunction "ET1_5") (pintype "bidirectional"))
      (node (ref "IC1") (pin "7") (pinfunction "ET2_7") (pintype "bidirectional"))
      (node (ref "IC2") (pin "5") (pinfunction "ET1_5") (pintype "bidirectional"))
      (node (ref "IC2") (pin "7") (pinfunction "ET2_7") (pintype "bidirectional"))
      (node (ref "IC4") (pin "1") (pinfunction "GND_1") (pintype "input"))
      (node (ref "J2") (pin "C5") (pinfunction "GND_C5") (pintype "power_in"))
      (node (ref "LED1") (pin "C") (pinfunction "C_C") (pintype "passive"))
      (node (ref "PS1") (pin "5") (pinfunction "0V_5") (pintype "output"))
      (node (ref "R1") (pin "1") (pinfunction "R1_1") (pintype "passive"))
      (node (ref "R2") (pin "2") (pinfunction "2_2") (pintype "passive"))
      (node (ref "R3") (pin "2") (pinfunction "2_2") (pintype "passive"))
      (node (ref "R5") (pin "2") (pinfunction "2_2") (pintype "passive"))
      (node (ref "T1") (pin "2") (pinfunction "E_2") (pintype "passive"))
      (node (ref "T2") (pin "2") (pinfunction "E_2") (pintype "passive"))
      (node (ref "T3") (pin "2") (pinfunction "E_2") (pintype "passive"))
      (node (ref "U$1") (pin "14") (pinfunction "14_14") (pintype "passive"))
      (node (ref "U$1") (pin "20") (pinfunction "20_20") (pintype "passive"))
      (node (ref "U$1") (pin "25") (pinfunction "25_25") (pintype "passive"))
      (node (ref "U$1") (pin "6") (pinfunction "6_6") (pintype "passive"))
      (node (ref "U$10") (pin "1") (pinfunction "1_1") (pintype "bidirectional"))
      (node (ref "U$2") (pin "5") (pinfunction "GND_5") (pintype "bidirectional"))
      (node (ref "U$3") (pin "P5") (pinfunction "OV_P5") (pintype "output"))
      (node (ref "U$4") (pin "P$3") (pinfunction "P$3_P$3") (pintype "bidirectional"))
      (node (ref "U$4") (pin "P$4") (pinfunction "P$4_P$4") (pintype "bidirectional"))
      (node (ref "U$5") (pin "1") (pinfunction "1_1") (pintype "bidirectional"))
      (node (ref "U$6") (pin "DC-") (pinfunction "DC-_DC-") (pintype "bidirectional"))
      (node (ref "U$7") (pin "1") (pinfunction "1_1") (pintype "bidirectional"))
      (node (ref "U$9") (pin "1") (pinfunction "1_1") (pintype "bidirectional"))
      (node (ref "USB_MODEM") (pin "1") (pinfunction "1_1") (pintype "bidirectional"))
      (node (ref "X2*1775838-2") (pin "15") (pinfunction "S_15") (pintype "passive"))
      (node (ref "X2*1775838-2") (pin "18") (pinfunction "S_18") (pintype "passive"))
      (node (ref "X2*1775838-2") (pin "26") (pinfunction "S_26") (pintype "passive"))
      (node (ref "X2*1775838-2") (pin "34") (pinfunction "S_34") (pintype "passive"))
      (node (ref "X2*1775838-2") (pin "4") (pinfunction "S_4") (pintype "passive"))
      (node (ref "X2*1775838-2") (pin "50") (pinfunction "S_50") (pintype "passive"))
      (node (ref "X2*1775838-2") (pin "9") (pinfunction "S_9") (pintype "passive"))
    )
    (net (code "59") (name "GND-CAR") (class "Default")
      (node (ref "9-36IN2") (pin "P$1") (pinfunction "P1_P$1") (pintype "bidirectional"))
      (node (ref "C2") (pin "-") (pinfunction "-_-") (pintype "passive"))
      (node (ref "C3") (pin "1") (pinfunction "C1_1") (pintype "passive"))
      (node (ref "C4") (pin "-") (pinfunction "-_-") (pintype "passive"))
      (node (ref "C5") (pin "C") (pinfunction "-_C") (pintype "passive"))
      (node (ref "PS1") (pin "2") (pinfunction "GND_2") (pintype "power_in"))
      (node (ref "R18") (pin "1") (pinfunction "R1_1") (pintype "passive"))
      (node (ref "R19") (pin "2") (pinfunction "R2_2") (pintype "passive"))
      (node (ref "R20") (pin "1") (pinfunction "R1_1") (pintype "passive"))
      (node (ref "R21") (pin "2") (pinfunction "R2_2") (pintype "passive"))
      (node (ref "R25") (pin "1") (pinfunction "R1_1") (pintype "passive"))
      (node (ref "R26") (pin "2") (pinfunction "R2_2") (pintype "passive"))
      (node (ref "R27") (pin "1") (pinfunction "R1_1") (pintype "passive"))
      (node (ref "R4") (pin "2") (pinfunction "R2_2") (pintype "passive"))
      (node (ref "U$3") (pin "P1") (pinfunction "GND_P1") (pintype "bidirectional"))
    )
    (net (code "60") (name "Net-(IC1-C1)") (class "Default")
      (node (ref "IC1") (pin "2") (pinfunction "C1_2") (pintype "bidirectional"))
      (node (ref "R20") (pin "2") (pinfunction "R2_2") (pintype "passive"))
    )
    (net (code "61") (name "Net-(IC1-C2)") (class "Default")
      (node (ref "IC1") (pin "4") (pinfunction "C2_4") (pintype "bidirectional"))
      (node (ref "R18") (pin "2") (pinfunction "R2_2") (pintype "passive"))
    )
    (net (code "62") (name "Net-(IC2-C1)") (class "Default")
      (node (ref "IC2") (pin "2") (pinfunction "C1_2") (pintype "bidirectional"))
      (node (ref "R27") (pin "2") (pinfunction "R2_2") (pintype "passive"))
    )
    (net (code "63") (name "Net-(IC2-C2)") (class "Default")
      (node (ref "IC2") (pin "4") (pinfunction "C2_4") (pintype "bidirectional"))
      (node (ref "R25") (pin "2") (pinfunction "R2_2") (pintype "passive"))
    )
    (net (code "64") (name "Net-(LED1-PadA)") (class "Default")
      (node (ref "LED1") (pin "A") (pinfunction "A_A") (pintype "passive"))
      (node (ref "R6") (pin "2") (pinfunction "2_2") (pintype "passive"))
    )
    (net (code "65") (name "Net-(LED2-PadC)") (class "Default")
      (node (ref "LED2") (pin "C") (pinfunction "C_C") (pintype "passive"))
      (node (ref "R2") (pin "1") (pinfunction "1_1") (pintype "passive"))
    )
    (net (code "66") (name "Net-(LED3-PadC)") (class "Default")
      (node (ref "LED3") (pin "C") (pinfunction "C_C") (pintype "passive"))
      (node (ref "R3") (pin "1") (pinfunction "1_1") (pintype "passive"))
    )
    (net (code "67") (name "Net-(LED4-PadC)") (class "Default")
      (node (ref "LED4") (pin "C") (pinfunction "C_C") (pintype "passive"))
      (node (ref "R5") (pin "1") (pinfunction "1_1") (pintype "passive"))
    )
    (net (code "68") (name "Net-(T1-B)") (class "Default")
      (node (ref "R14") (pin "2") (pinfunction "2_2") (pintype "passive"))
      (node (ref "T1") (pin "1") (pinfunction "B_1") (pintype "passive"))
    )
    (net (code "69") (name "Net-(T1-C)") (class "Default")
      (node (ref "CON12V") (pin "1") (pinfunction "1_1") (pintype "passive"))
      (node (ref "T1") (pin "3") (pinfunction "C_3") (pintype "passive"))
    )
    (net (code "70") (name "Net-(T2-B)") (class "Default")
      (node (ref "R13") (pin "2") (pinfunction "2_2") (pintype "passive"))
      (node (ref "T2") (pin "1") (pinfunction "B_1") (pintype "passive"))
    )
    (net (code "71") (name "Net-(T2-C)") (class "Default")
      (node (ref "MODEM") (pin "1") (pinfunction "1_1") (pintype "passive"))
      (node (ref "T2") (pin "3") (pinfunction "C_3") (pintype "passive"))
    )
    (net (code "72") (name "Net-(T3-B)") (class "Default")
      (node (ref "R15") (pin "2") (pinfunction "2_2") (pintype "passive"))
      (node (ref "T3") (pin "1") (pinfunction "B_1") (pintype "passive"))
    )
    (net (code "73") (name "Net-(T3-C)") (class "Default")
      (node (ref "GPS") (pin "1") (pinfunction "1_1") (pintype "passive"))
      (node (ref "T3") (pin "3") (pinfunction "C_3") (pintype "passive"))
    )
    (net (code "74") (name "unconnected-(PS1-CTRL-Pad3)") (class "Default")
      (node (ref "PS1") (pin "3") (pinfunction "CTRL_3") (pintype "input"))
    )
    (net (code "75") (name "unconnected-(PS1-TRIM-Pad4)") (class "Default")
      (node (ref "PS1") (pin "4") (pinfunction "TRIM_4") (pintype "input"))
    )
    (net (code "76") (name "unconnected-(U$1-Pad3)") (class "Default")
      (node (ref "U$1") (pin "3") (pinfunction "3_3") (pintype "passive"))
    )
    (net (code "77") (name "unconnected-(U$1-Pad4)") (class "Default")
      (node (ref "U$1") (pin "4") (pinfunction "4_4") (pintype "passive"))
    )
    (net (code "78") (name "unconnected-(U$1-Pad5)") (class "Default")
      (node (ref "U$1") (pin "5") (pinfunction "5_5") (pintype "passive"))
    )
    (net (code "79") (name "unconnected-(U$1-Pad7)") (class "Default")
      (node (ref "U$1") (pin "7") (pinfunction "7_7") (pintype "passive"))
    )
    (net (code "80") (name "unconnected-(U$1-Pad9)") (class "Default")
      (node (ref "U$1") (pin "9") (pinfunction "9_9") (pintype "passive"))
    )
    (net (code "81") (name "unconnected-(U$1-Pad11)") (class "Default")
      (node (ref "U$1") (pin "11") (pinfunction "11_11") (pintype "passive"))
    )
    (net (code "82") (name "unconnected-(U$1-Pad13)") (class "Default")
      (node (ref "U$1") (pin "13") (pinfunction "13_13") (pintype "passive"))
    )
    (net (code "83") (name "unconnected-(U$1-Pad16)") (class "Default")
      (node (ref "U$1") (pin "16") (pinfunction "16_16") (pintype "passive"))
    )
    (net (code "84") (name "unconnected-(U$1-Pad17)") (class "Default")
      (node (ref "U$1") (pin "17") (pinfunction "17_17") (pintype "passive"))
    )
    (net (code "85") (name "unconnected-(U$1-Pad18)") (class "Default")
      (node (ref "U$1") (pin "18") (pinfunction "18_18") (pintype "passive"))
    )
    (net (code "86") (name "unconnected-(U$1-Pad19)") (class "Default")
      (node (ref "U$1") (pin "19") (pinfunction "19_19") (pintype "passive"))
    )
    (net (code "87") (name "unconnected-(U$1-Pad21)") (class "Default")
      (node (ref "U$1") (pin "21") (pinfunction "21_21") (pintype "passive"))
    )
    (net (code "88") (name "unconnected-(U$1-Pad22)") (class "Default")
      (node (ref "U$1") (pin "22") (pinfunction "22_22") (pintype "passive"))
    )
    (net (code "89") (name "unconnected-(U$1-Pad24)") (class "Default")
      (node (ref "U$1") (pin "24") (pinfunction "24_24") (pintype "passive"))
    )
    (net (code "90") (name "unconnected-(U$1-Pad26)") (class "Default")
      (node (ref "U$1") (pin "26") (pinfunction "26_26") (pintype "passive"))
    )
    (net (code "91") (name "unconnected-(U$1-Pad27)") (class "Default")
      (node (ref "U$1") (pin "27") (pinfunction "27_27") (pintype "passive"))
    )
    (net (code "92") (name "unconnected-(U$1-Pad28)") (class "Default")
      (node (ref "U$1") (pin "28") (pinfunction "28_28") (pintype "passive"))
    )
    (net (code "93") (name "unconnected-(U$1-Pad30)") (class "Default")
      (node (ref "U$1") (pin "30") (pinfunction "30_30") (pintype "passive"))
    )
    (net (code "94") (name "unconnected-(U$1-Pad32)") (class "Default")
      (node (ref "U$1") (pin "32") (pinfunction "32_32") (pintype "passive"))
    )
    (net (code "95") (name "unconnected-(U$1-Pad34)") (class "Default")
      (node (ref "U$1") (pin "34") (pinfunction "34_34") (pintype "passive"))
    )
    (net (code "96") (name "unconnected-(U$1-Pad35)") (class "Default")
      (node (ref "U$1") (pin "35") (pinfunction "35_35") (pintype "passive"))
    )
    (net (code "97") (name "unconnected-(U$1-Pad36)") (class "Default")
      (node (ref "U$1") (pin "36") (pinfunction "36_36") (pintype "passive"))
    )
    (net (code "98") (name "unconnected-(U$1-Pad37)") (class "Default")
      (node (ref "U$1") (pin "37") (pinfunction "37_37") (pintype "passive"))
    )
    (net (code "99") (name "unconnected-(U$1-Pad38)") (class "Default")
      (node (ref "U$1") (pin "38") (pinfunction "38_38") (pintype "passive"))
    )
    (net (code "100") (name "unconnected-(U$1-Pad39)") (class "Default")
      (node (ref "U$1") (pin "39") (pinfunction "39_39") (pintype "passive"))
    )
    (net (code "101") (name "unconnected-(U$1-Pad40)") (class "Default")
      (node (ref "U$1") (pin "40") (pinfunction "40_40") (pintype "passive"))
    )
    (net (code "102") (name "unconnected-(U$3-CTRL-PadP6)") (class "Default")
      (node (ref "U$3") (pin "P6") (pinfunction "CTRL_P6") (pintype "bidirectional"))
    )
    (net (code "103") (name "unconnected-(U$3-NC-PadP4)") (class "Default")
      (node (ref "U$3") (pin "P4") (pinfunction "NC_P4") (pintype "output"))
    )
    (net (code "104") (name "unconnected-(X2*1775838-2A-S-Pad1)") (class "Default")
      (node (ref "X2*1775838-2") (pin "1") (pinfunction "S_1") (pintype "passive"))
    )
    (net (code "105") (name "unconnected-(X2*1775838-2AA-S-Pad33)") (class "Default")
      (node (ref "X2*1775838-2") (pin "33") (pinfunction "S_33") (pintype "passive"))
    )
    (net (code "106") (name "unconnected-(X2*1775838-2AC-S-Pad35)") (class "Default")
      (node (ref "X2*1775838-2") (pin "35") (pinfunction "S_35") (pintype "passive"))
    )
    (net (code "107") (name "unconnected-(X2*1775838-2AE-S-Pad37)") (class "Default")
      (node (ref "X2*1775838-2") (pin "37") (pinfunction "S_37") (pintype "passive"))
    )
    (net (code "108") (name "unconnected-(X2*1775838-2AG-S-Pad39)") (class "Default")
      (node (ref "X2*1775838-2") (pin "39") (pinfunction "S_39") (pintype "passive"))
    )
    (net (code "109") (name "unconnected-(X2*1775838-2AI-S-Pad40)") (class "Default")
      (node (ref "X2*1775838-2") (pin "40") (pinfunction "S_40") (pintype "passive"))
    )
    (net (code "110") (name "unconnected-(X2*1775838-2AJ-S-Pad41)") (class "Default")
      (node (ref "X2*1775838-2") (pin "41") (pinfunction "S_41") (pintype "passive"))
    )
    (net (code "111") (name "unconnected-(X2*1775838-2AL-S-Pad43)") (class "Default")
      (node (ref "X2*1775838-2") (pin "43") (pinfunction "S_43") (pintype "passive"))
    )
    (net (code "112") (name "unconnected-(X2*1775838-2AM-S-Pad44)") (class "Default")
      (node (ref "X2*1775838-2") (pin "44") (pinfunction "S_44") (pintype "passive"))
    )
    (net (code "113") (name "unconnected-(X2*1775838-2AN-S-Pad45)") (class "Default")
      (node (ref "X2*1775838-2") (pin "45") (pinfunction "S_45") (pintype "passive"))
    )
    (net (code "114") (name "unconnected-(X2*1775838-2AO-S-Pad46)") (class "Default")
      (node (ref "X2*1775838-2") (pin "46") (pinfunction "S_46") (pintype "passive"))
    )
    (net (code "115") (name "unconnected-(X2*1775838-2AP-S-Pad47)") (class "Default")
      (node (ref "X2*1775838-2") (pin "47") (pinfunction "S_47") (pintype "passive"))
    )
    (net (code "116") (name "unconnected-(X2*1775838-2AQ-S-Pad48)") (class "Default")
      (node (ref "X2*1775838-2") (pin "48") (pinfunction "S_48") (pintype "passive"))
    )
    (net (code "117") (name "unconnected-(X2*1775838-2AR-S-Pad49)") (class "Default")
      (node (ref "X2*1775838-2") (pin "49") (pinfunction "S_49") (pintype "passive"))
    )
    (net (code "118") (name "unconnected-(X2*1775838-2AS-S-Pad5)") (class "Default")
      (node (ref "X2*1775838-2") (pin "5") (pinfunction "S_5") (pintype "passive"))
    )
    (net (code "119") (name "unconnected-(X2*1775838-2AU-S-Pad51)") (class "Default")
      (node (ref "X2*1775838-2") (pin "51") (pinfunction "S_51") (pintype "passive"))
    )
    (net (code "120") (name "unconnected-(X2*1775838-2AW-S-Pad6)") (class "Default")
      (node (ref "X2*1775838-2") (pin "6") (pinfunction "S_6") (pintype "passive"))
    )
    (net (code "121") (name "unconnected-(X2*1775838-2AX-S-Pad7)") (class "Default")
      (node (ref "X2*1775838-2") (pin "7") (pinfunction "S_7") (pintype "passive"))
    )
    (net (code "122") (name "unconnected-(X2*1775838-2C-S-Pad11)") (class "Default")
      (node (ref "X2*1775838-2") (pin "11") (pinfunction "S_11") (pintype "passive"))
    )
    (net (code "123") (name "unconnected-(X2*1775838-2E-S-Pad13)") (class "Default")
      (node (ref "X2*1775838-2") (pin "13") (pinfunction "S_13") (pintype "passive"))
    )
    (net (code "124") (name "unconnected-(X2*1775838-2I-S-Pad17)") (class "Default")
      (node (ref "X2*1775838-2") (pin "17") (pinfunction "S_17") (pintype "passive"))
    )
    (net (code "125") (name "unconnected-(X2*1775838-2K-S-Pad19)") (class "Default")
      (node (ref "X2*1775838-2") (pin "19") (pinfunction "S_19") (pintype "passive"))
    )
    (net (code "126") (name "unconnected-(X2*1775838-2M-S-Pad20)") (class "Default")
      (node (ref "X2*1775838-2") (pin "20") (pinfunction "S_20") (pintype "passive"))
    )
    (net (code "127") (name "unconnected-(X2*1775838-2N-S-Pad21)") (class "Default")
      (node (ref "X2*1775838-2") (pin "21") (pinfunction "S_21") (pintype "passive"))
    )
    (net (code "128") (name "unconnected-(X2*1775838-2O-S-Pad22)") (class "Default")
      (node (ref "X2*1775838-2") (pin "22") (pinfunction "S_22") (pintype "passive"))
    )
    (net (code "129") (name "unconnected-(X2*1775838-2P-S-Pad23)") (class "Default")
      (node (ref "X2*1775838-2") (pin "23") (pinfunction "S_23") (pintype "passive"))
    )
    (net (code "130") (name "unconnected-(X2*1775838-2Q-S-Pad24)") (class "Default")
      (node (ref "X2*1775838-2") (pin "24") (pinfunction "S_24") (pintype "passive"))
    )
    (net (code "131") (name "unconnected-(X2*1775838-2R-S-Pad25)") (class "Default")
      (node (ref "X2*1775838-2") (pin "25") (pinfunction "S_25") (pintype "passive"))
    )
    (net (code "132") (name "unconnected-(X2*1775838-2T-S-Pad27)") (class "Default")
      (node (ref "X2*1775838-2") (pin "27") (pinfunction "S_27") (pintype "passive"))
    )
    (net (code "133") (name "unconnected-(X2*1775838-2U-S-Pad28)") (class "Default")
      (node (ref "X2*1775838-2") (pin "28") (pinfunction "S_28") (pintype "passive"))
    )
    (net (code "134") (name "unconnected-(X2*1775838-2V-S-Pad29)") (class "Default")
      (node (ref "X2*1775838-2") (pin "29") (pinfunction "S_29") (pintype "passive"))
    )
    (net (code "135") (name "unconnected-(X2*1775838-2W-S-Pad3)") (class "Default")
      (node (ref "X2*1775838-2") (pin "3") (pinfunction "S_3") (pintype "passive"))
    )
    (net (code "136") (name "unconnected-(X2*1775838-2X-S-Pad30)") (class "Default")
      (node (ref "X2*1775838-2") (pin "30") (pinfunction "S_30") (pintype "passive"))
    )
    (net (code "137") (name "unconnected-(X2*1775838-2Y-S-Pad31)") (class "Default")
      (node (ref "X2*1775838-2") (pin "31") (pinfunction "S_31") (pintype "passive"))
    )
    (net (code "138") (name "unconnected-(X2*1775838-2Z-S-Pad32)") (class "Default")
      (node (ref "X2*1775838-2") (pin "32") (pinfunction "S_32") (pintype "passive"))
    )
  )
)
